# VoltSensor.net
KiCad netlist of a schematic drawn in EAGLE
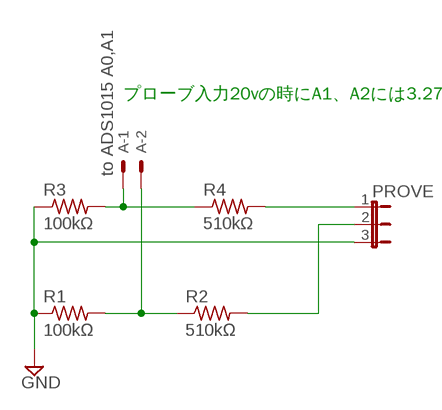
[diagram p0: schematic, sheet 1]

(export (version "E")
  (design (tool "Eeschema 10.0.6"))
  (components
    (comp (ref "A")
      (value "to ADS1015 A0,A1")
      (footprint "eagle-import:22-23-2021")
      (fields (field (name "MF") "MOLEX") (field (name "MPN") "22-23-2021"))
      (libsource (lib "eagle-import") (part "22-23-2021"))
    )
    (comp (ref "PROVE")
      (value "JP2E")
      (footprint "eagle-import:JP2")
      (libsource (lib "eagle-import") (part "JP2E"))
    )
    (comp (ref "R1")
      (value "100kΩ")
      (footprint "eagle-import:M1206")
      (libsource (lib "eagle-import") (part "R-US_M1206"))
    )
    (comp (ref "R2")
      (value "510kΩ")
      (footprint "eagle-import:M1206")
      (libsource (lib "eagle-import") (part "R-US_M1206"))
    )
    (comp (ref "R3")
      (value "100kΩ")
      (footprint "eagle-import:M1206")
      (libsource (lib "eagle-import") (part "R-US_M1206"))
    )
    (comp (ref "R4")
      (value "510kΩ")
      (footprint "eagle-import:M1206")
      (libsource (lib "eagle-import") (part "R-US_M1206"))
    )
  )
  (nets
    (net (code "1") (name "GND") (class "Default")
      (node (ref "PROVE") (pin "3") (pinfunction "3_3") (pintype "passive"))
      (node (ref "R1") (pin "1") (pinfunction "1_1") (pintype "passive"))
      (node (ref "R3") (pin "1") (pinfunction "1_1") (pintype "passive"))
    )
    (net (code "2") (name "Net-(AA-S)") (class "Default")
      (node (ref "A") (pin "1") (pinfunction "S_1") (pintype "passive"))
      (node (ref "R3") (pin "2") (pinfunction "2_2") (pintype "passive"))
      (node (ref "R4") (pin "1") (pinfunction "1_1") (pintype "passive"))
    )
    (net (code "3") (name "Net-(AB-S)") (class "Default")
      (node (ref "A") (pin "2") (pinfunction "S_2") (pintype "passive"))
      (node (ref "R1") (pin "2") (pinfunction "2_2") (pintype "passive"))
      (node (ref "R2") (pin "1") (pinfunction "1_1") (pintype "passive"))
    )
    (net (code "4") (name "Net-(PROVE-Pad1)") (class "Default")
      (node (ref "PROVE") (pin "1") (pinfunction "1_1") (pintype "passive"))
      (node (ref "R4") (pin "2") (pinfunction "2_2") (pintype "passive"))
    )
    (net (code "5") (name "Net-(PROVE-Pad2)") (class "Default")
      (node (ref "PROVE") (pin "2") (pinfunction "2_2") (pintype "passive"))
      (node (ref "R2") (pin "2") (pinfunction "2_2") (pintype "passive"))
    )
  )
)
